# arduino-shield-xyzhbridge-stepper-v1.net
KiCad netlist of a schematic drawn in EAGLE
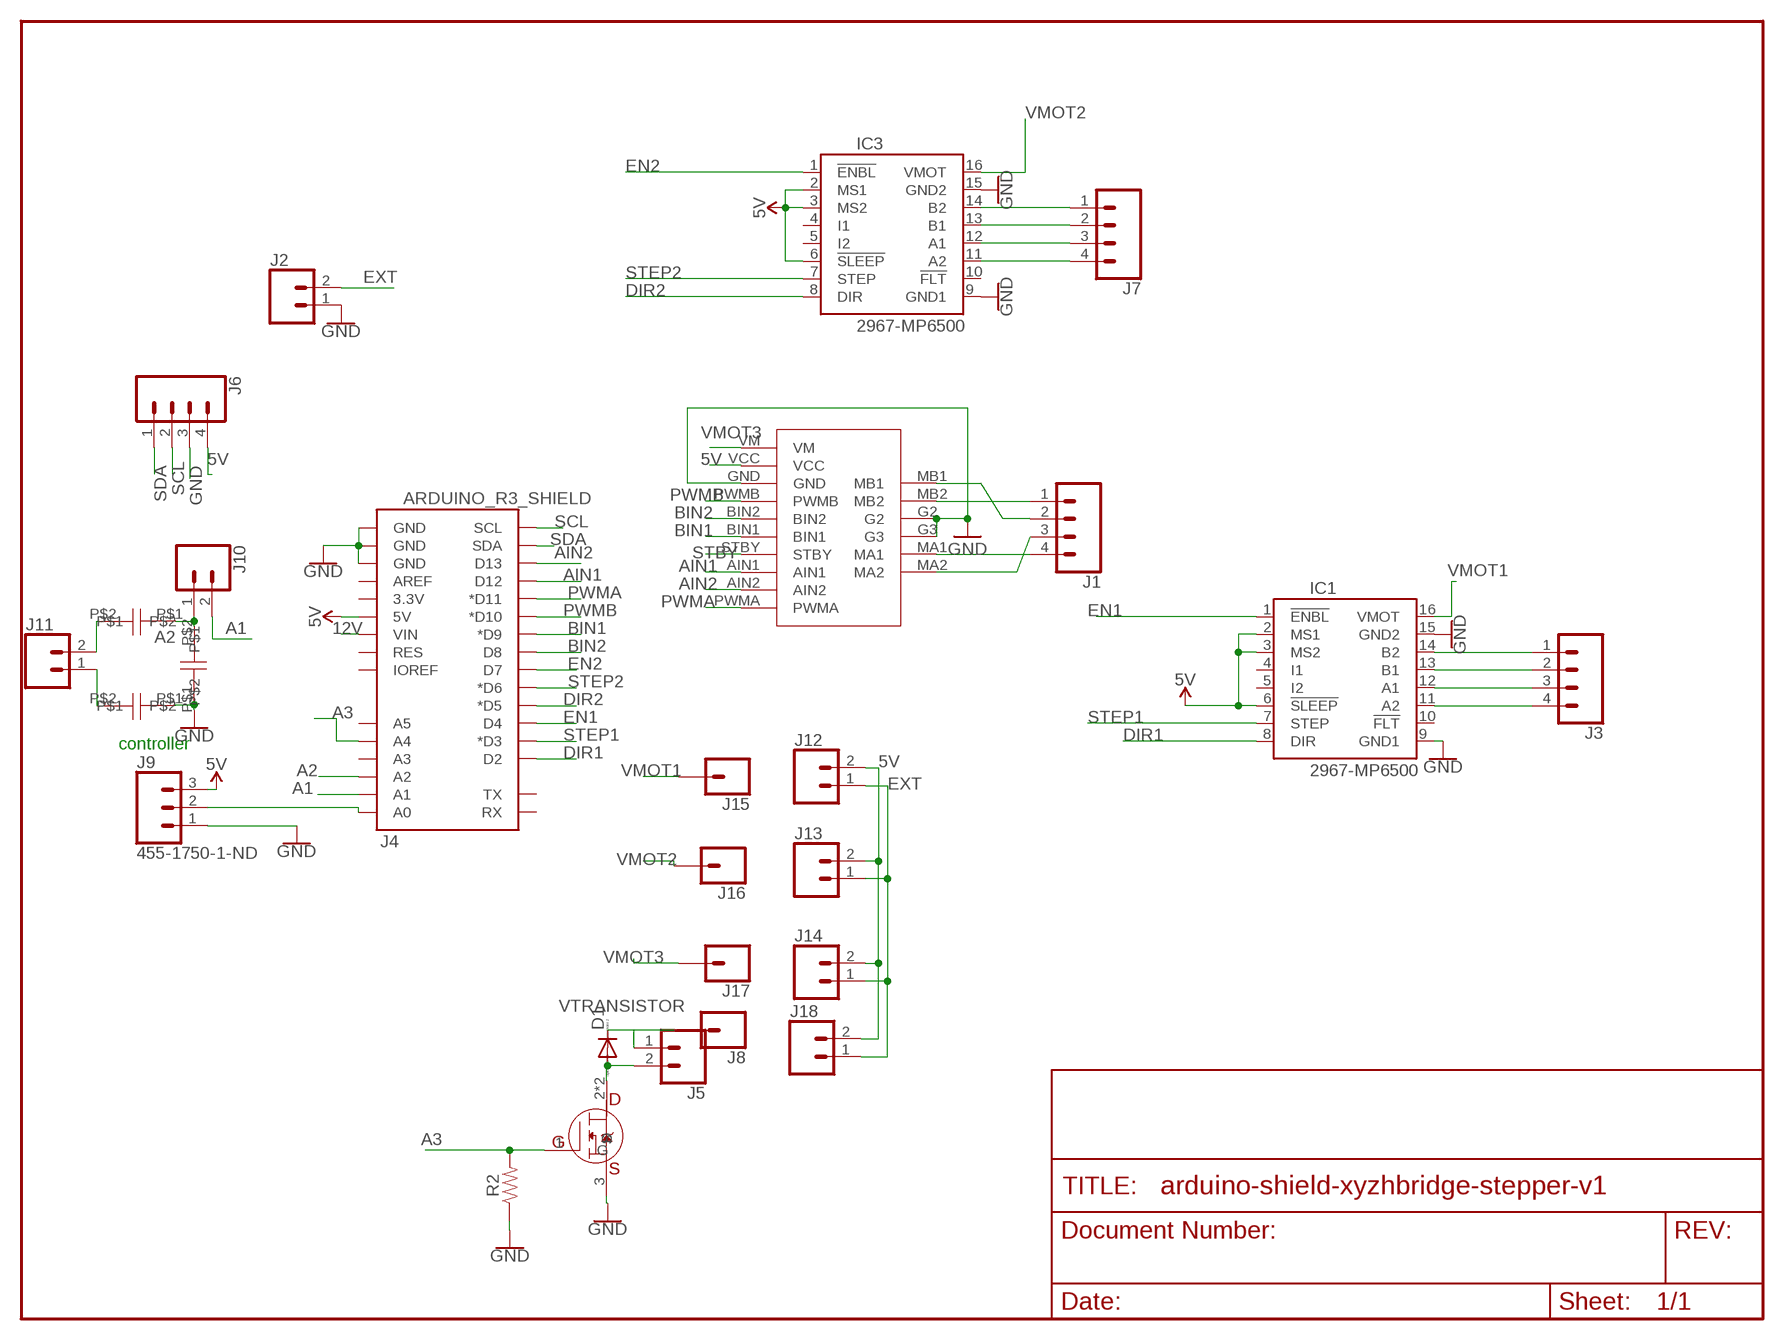
[diagram p0: schematic, sheet 1]

(export (version "E")
  (design (tool "Eeschema 10.0.6"))
  (components
    (comp (ref "D1")
      (value "DIODE-DO-214AC")
      (footprint "eagle-import:DO-214AC")
      (libsource (lib "eagle-import") (part "DIODE-DO-214AC"))
    )
    (comp (ref "IC1")
      (value "2967-MP6500")
      (footprint "eagle-import:MP6500")
      (libsource (lib "eagle-import") (part "2967-MP6500"))
    )
    (comp (ref "IC3")
      (value "2967-MP6500")
      (footprint "eagle-import:MP6500")
      (libsource (lib "eagle-import") (part "2967-MP6500"))
    )
    (comp (ref "J1")
      (value "CONN_04")
      (footprint "eagle-import:1X04")
      (libsource (lib "eagle-import") (part "CONN_04"))
    )
    (comp (ref "J2")
      (value "CONN_02")
      (footprint "eagle-import:1X02")
      (libsource (lib "eagle-import") (part "CONN_02"))
    )
    (comp (ref "J3")
      (value "CONN_04")
      (footprint "eagle-import:1X04")
      (libsource (lib "eagle-import") (part "CONN_04"))
    )
    (comp (ref "J4")
      (value "ARDUINO_R3_SHIELD")
      (footprint "eagle-import:UNO_R3_SHIELD")
      (libsource (lib "eagle-import") (part "ARDUINO_R3_SHIELD"))
    )
    (comp (ref "J5")
      (value "CONN_02")
      (footprint "eagle-import:1X02")
      (libsource (lib "eagle-import") (part "CONN_02"))
    )
    (comp (ref "J6")
      (value "CONN_04")
      (footprint "eagle-import:1X04")
      (libsource (lib "eagle-import") (part "CONN_04"))
    )
    (comp (ref "J7")
      (value "CONN_04")
      (footprint "eagle-import:1X04")
      (libsource (lib "eagle-import") (part "CONN_04"))
    )
    (comp (ref "J8")
      (value "CONN_01")
      (footprint "eagle-import:1X01")
      (libsource (lib "eagle-import") (part "CONN_01"))
    )
    (comp (ref "J9")
      (value "455-1750-1-ND")
      (footprint "eagle-import:1X03")
      (libsource (lib "eagle-import") (part "CONN_03"))
    )
    (comp (ref "J10")
      (value "CONN_02")
      (footprint "eagle-import:1X02")
      (libsource (lib "eagle-import") (part "CONN_02"))
    )
    (comp (ref "J11")
      (value "CONN_02")
      (footprint "eagle-import:1X02")
      (libsource (lib "eagle-import") (part "CONN_02"))
    )
    (comp (ref "J12")
      (value "CONN_02")
      (footprint "eagle-import:1X02")
      (libsource (lib "eagle-import") (part "CONN_02"))
    )
    (comp (ref "J13")
      (value "CONN_02")
      (footprint "eagle-import:1X02")
      (libsource (lib "eagle-import") (part "CONN_02"))
    )
    (comp (ref "J14")
      (value "CONN_02")
      (footprint "eagle-import:1X02")
      (libsource (lib "eagle-import") (part "CONN_02"))
    )
    (comp (ref "J15")
      (value "CONN_01")
      (footprint "eagle-import:1X01")
      (libsource (lib "eagle-import") (part "CONN_01"))
    )
    (comp (ref "J16")
      (value "CONN_01")
      (footprint "eagle-import:1X01")
      (libsource (lib "eagle-import") (part "CONN_01"))
    )
    (comp (ref "J17")
      (value "CONN_01")
      (footprint "eagle-import:1X01")
      (libsource (lib "eagle-import") (part "CONN_01"))
    )
    (comp (ref "J18")
      (value "CONN_02")
      (footprint "eagle-import:1X02")
      (libsource (lib "eagle-import") (part "CONN_02"))
    )
    (comp (ref "R2")
      (value "RESISTORAXIAL-0.3")
      (footprint "eagle-import:AXIAL-0.3")
      (libsource (lib "eagle-import") (part "RESISTORAXIAL-0.3"))
    )
    (comp (ref "U$1")
      (value "ADAFRUIT-TB6612")
      (footprint "eagle-import:ADAFRUIT-TB6612")
      (libsource (lib "eagle-import") (part "ADAFRUIT-TB6612"))
    )
    (comp (ref "U$2")
      (value "AXIALCAP")
      (footprint "eagle-import:AXIALCAP")
      (libsource (lib "eagle-import") (part "AXIALCAP"))
    )
    (comp (ref "U$3")
      (value "AXIALCAP")
      (footprint "eagle-import:AXIALCAP")
      (libsource (lib "eagle-import") (part "AXIALCAP"))
    )
    (comp (ref "U$4")
      (value "AXIALCAP")
      (footprint "eagle-import:AXIALCAP")
      (libsource (lib "eagle-import") (part "AXIALCAP"))
    )
    (comp (ref "U$5")
      (value "IRFL024NPBF")
      (footprint "eagle-import:SOT223")
      (libsource (lib "eagle-import") (part "IRFL024NPBF"))
    )
  )
  (nets
    (net (code "1") (name "/12V") (class "Default")
      (node (ref "J4") (pin "VIN") (pinfunction "VIN_VIN") (pintype "bidirectional"))
    )
    (net (code "2") (name "/A1") (class "Default")
      (node (ref "J10") (pin "2") (pinfunction "2_2") (pintype "passive"))
      (node (ref "J4") (pin "A1") (pinfunction "A1_A1") (pintype "bidirectional"))
    )
    (net (code "3") (name "/A2") (class "Default")
      (node (ref "J10") (pin "1") (pinfunction "1_1") (pintype "passive"))
      (node (ref "J4") (pin "A2") (pinfunction "A2_A2") (pintype "bidirectional"))
      (node (ref "U$3") (pin "P$2") (pinfunction "P$2_P$2") (pintype "bidirectional"))
      (node (ref "U$4") (pin "P$1") (pinfunction "P$1_P$1") (pintype "bidirectional"))
    )
    (net (code "4") (name "/A3") (class "Default")
      (node (ref "J4") (pin "A4") (pinfunction "A4_A4") (pintype "bidirectional"))
      (node (ref "R2") (pin "P$2") (pinfunction "2_P$2") (pintype "passive"))
      (node (ref "U$5") (pin "1") (pinfunction "G_1") (pintype "bidirectional"))
    )
    (net (code "5") (name "/AIN1") (class "Default")
      (node (ref "J4") (pin "D12") (pinfunction "D12_D12") (pintype "bidirectional"))
      (node (ref "U$1") (pin "AIN1") (pinfunction "AIN1_AIN1") (pintype "bidirectional"))
    )
    (net (code "6") (name "/AIN2") (class "Default")
      (node (ref "J4") (pin "D13") (pinfunction "D13_D13") (pintype "bidirectional"))
      (node (ref "U$1") (pin "AIN2") (pinfunction "AIN2_AIN2") (pintype "bidirectional"))
    )
    (net (code "7") (name "/BIN1") (class "Default")
      (node (ref "J4") (pin "D9") (pinfunction "*D9_D9") (pintype "bidirectional"))
      (node (ref "U$1") (pin "BIN1") (pinfunction "BIN1_BIN1") (pintype "bidirectional"))
    )
    (net (code "8") (name "/BIN2") (class "Default")
      (node (ref "J4") (pin "D8") (pinfunction "D8_D8") (pintype "bidirectional"))
      (node (ref "U$1") (pin "BIN2") (pinfunction "BIN2_BIN2") (pintype "bidirectional"))
    )
    (net (code "9") (name "/DIR1") (class "Default")
      (node (ref "IC1") (pin "8") (pinfunction "DIR_8") (pintype "input"))
      (node (ref "J4") (pin "D2") (pinfunction "D2_D2") (pintype "bidirectional"))
    )
    (net (code "10") (name "/DIR2") (class "Default")
      (node (ref "IC3") (pin "8") (pinfunction "DIR_8") (pintype "input"))
      (node (ref "J4") (pin "D5") (pinfunction "*D5_D5") (pintype "bidirectional"))
    )
    (net (code "11") (name "/EN1") (class "Default")
      (node (ref "IC1") (pin "1") (pinfunction "~{ENBL}_1") (pintype "passive"))
      (node (ref "J4") (pin "D4") (pinfunction "D4_D4") (pintype "bidirectional"))
    )
    (net (code "12") (name "/EN2") (class "Default")
      (node (ref "IC3") (pin "1") (pinfunction "~{ENBL}_1") (pintype "passive"))
      (node (ref "J4") (pin "D7") (pinfunction "D7_D7") (pintype "bidirectional"))
    )
    (net (code "13") (name "/EXT") (class "Default")
      (node (ref "J12") (pin "1") (pinfunction "1_1") (pintype "passive"))
      (node (ref "J13") (pin "1") (pinfunction "1_1") (pintype "passive"))
      (node (ref "J14") (pin "1") (pinfunction "1_1") (pintype "passive"))
      (node (ref "J18") (pin "1") (pinfunction "1_1") (pintype "passive"))
      (node (ref "J2") (pin "2") (pinfunction "2_2") (pintype "passive"))
    )
    (net (code "14") (name "/PWMA") (class "Default")
      (node (ref "J4") (pin "D11") (pinfunction "*D11_D11") (pintype "bidirectional"))
      (node (ref "U$1") (pin "PWMA") (pinfunction "PWMA_PWMA") (pintype "bidirectional"))
    )
    (net (code "15") (name "/PWMB") (class "Default")
      (node (ref "J4") (pin "D10") (pinfunction "*D10_D10") (pintype "bidirectional"))
      (node (ref "U$1") (pin "PWMB") (pinfunction "PWMB_PWMB") (pintype "bidirectional"))
    )
    (net (code "16") (name "/SCL") (class "Default")
      (node (ref "J4") (pin "SCL") (pinfunction "SCL_SCL") (pintype "bidirectional"))
      (node (ref "J6") (pin "2") (pinfunction "2_2") (pintype "passive"))
    )
    (net (code "17") (name "/SDA") (class "Default")
      (node (ref "J4") (pin "SDA") (pinfunction "SDA_SDA") (pintype "bidirectional"))
      (node (ref "J6") (pin "1") (pinfunction "1_1") (pintype "passive"))
    )
    (net (code "18") (name "/STBY") (class "Default")
      (node (ref "U$1") (pin "STBY") (pinfunction "STBY_STBY") (pintype "bidirectional"))
    )
    (net (code "19") (name "/STEP1") (class "Default")
      (node (ref "IC1") (pin "7") (pinfunction "STEP_7") (pintype "input"))
      (node (ref "J4") (pin "D3") (pinfunction "*D3_D3") (pintype "bidirectional"))
    )
    (net (code "20") (name "/STEP2") (class "Default")
      (node (ref "IC3") (pin "7") (pinfunction "STEP_7") (pintype "input"))
      (node (ref "J4") (pin "D6") (pinfunction "*D6_D6") (pintype "bidirectional"))
    )
    (net (code "21") (name "/VMOT1") (class "Default")
      (node (ref "IC1") (pin "16") (pinfunction "VMOT_16") (pintype "power_in"))
      (node (ref "J15") (pin "1") (pinfunction "1_1") (pintype "passive"))
    )
    (net (code "22") (name "/VMOT2") (class "Default")
      (node (ref "IC3") (pin "16") (pinfunction "VMOT_16") (pintype "power_in"))
      (node (ref "J16") (pin "1") (pinfunction "1_1") (pintype "passive"))
    )
    (net (code "23") (name "/VMOT3") (class "Default")
      (node (ref "J17") (pin "1") (pinfunction "1_1") (pintype "passive"))
      (node (ref "U$1") (pin "VM") (pinfunction "VM_VM") (pintype "bidirectional"))
    )
    (net (code "24") (name "/VTRANSISTOR") (class "Default")
      (node (ref "D1") (pin "C") (pinfunction "C_C") (pintype "passive"))
      (node (ref "J5") (pin "1") (pinfunction "1_1") (pintype "passive"))
      (node (ref "J8") (pin "1") (pinfunction "1_1") (pintype "passive"))
    )
    (net (code "25") (name "5V") (class "Default")
      (node (ref "IC1") (pin "2") (pinfunction "MS1_2") (pintype "passive"))
      (node (ref "IC1") (pin "3") (pinfunction "MS2_3") (pintype "passive"))
      (node (ref "IC1") (pin "6") (pinfunction "~{SLEEP}_6") (pintype "input"))
      (node (ref "IC3") (pin "2") (pinfunction "MS1_2") (pintype "passive"))
      (node (ref "IC3") (pin "3") (pinfunction "MS2_3") (pintype "passive"))
      (node (ref "IC3") (pin "6") (pinfunction "~{SLEEP}_6") (pintype "input"))
      (node (ref "J12") (pin "2") (pinfunction "2_2") (pintype "passive"))
      (node (ref "J13") (pin "2") (pinfunction "2_2") (pintype "passive"))
      (node (ref "J14") (pin "2") (pinfunction "2_2") (pintype "passive"))
      (node (ref "J18") (pin "2") (pinfunction "2_2") (pintype "passive"))
      (node (ref "J4") (pin "5V") (pinfunction "5V_5V") (pintype "bidirectional"))
      (node (ref "J6") (pin "4") (pinfunction "4_4") (pintype "passive"))
      (node (ref "J9") (pin "3") (pinfunction "3_3") (pintype "passive"))
      (node (ref "U$1") (pin "VCC") (pinfunction "VCC_VCC") (pintype "bidirectional"))
    )
    (net (code "26") (name "GND") (class "Default")
      (node (ref "IC1") (pin "15") (pinfunction "GND2_15") (pintype "power_in"))
      (node (ref "IC1") (pin "9") (pinfunction "GND1_9") (pintype "power_in"))
      (node (ref "IC3") (pin "15") (pinfunction "GND2_15") (pintype "power_in"))
      (node (ref "IC3") (pin "9") (pinfunction "GND1_9") (pintype "power_in"))
      (node (ref "J2") (pin "1") (pinfunction "1_1") (pintype "passive"))
      (node (ref "J4") (pin "GND@0") (pinfunction "GND_GND@0") (pintype "bidirectional"))
      (node (ref "J4") (pin "GND@1") (pinfunction "GND_GND@1") (pintype "bidirectional"))
      (node (ref "J4") (pin "GND@2") (pinfunction "GND_GND@2") (pintype "bidirectional"))
      (node (ref "J6") (pin "3") (pinfunction "3_3") (pintype "passive"))
      (node (ref "J9") (pin "1") (pinfunction "1_1") (pintype "passive"))
      (node (ref "R2") (pin "P$1") (pinfunction "1_P$1") (pintype "passive"))
      (node (ref "U$1") (pin "G2") (pinfunction "G2_G2") (pintype "bidirectional"))
      (node (ref "U$1") (pin "G3") (pinfunction "G3_G3") (pintype "bidirectional"))
      (node (ref "U$1") (pin "GND") (pinfunction "GND_GND") (pintype "bidirectional"))
      (node (ref "U$2") (pin "P$1") (pinfunction "P$1_P$1") (pintype "bidirectional"))
      (node (ref "U$3") (pin "P$1") (pinfunction "P$1_P$1") (pintype "bidirectional"))
      (node (ref "U$5") (pin "3") (pinfunction "S_3") (pintype "bidirectional"))
    )
    (net (code "27") (name "Net-(D1-PadA)") (class "Default")
      (node (ref "D1") (pin "A") (pinfunction "A_A") (pintype "passive"))
      (node (ref "J5") (pin "2") (pinfunction "2_2") (pintype "passive"))
      (node (ref "U$5") (pin "2") (pinfunction "D_2") (pintype "bidirectional"))
      (node (ref "U$5") (pin "4") (pinfunction "D_4") (pintype "bidirectional"))
    )
    (net (code "28") (name "Net-(IC1-A1)") (class "Default")
      (node (ref "IC1") (pin "12") (pinfunction "A1_12") (pintype "output"))
      (node (ref "J3") (pin "3") (pinfunction "3_3") (pintype "passive"))
    )
    (net (code "29") (name "Net-(IC1-A2)") (class "Default")
      (node (ref "IC1") (pin "11") (pinfunction "A2_11") (pintype "output"))
      (node (ref "J3") (pin "4") (pinfunction "4_4") (pintype "passive"))
    )
    (net (code "30") (name "Net-(IC1-B1)") (class "Default")
      (node (ref "IC1") (pin "13") (pinfunction "B1_13") (pintype "output"))
      (node (ref "J3") (pin "2") (pinfunction "2_2") (pintype "passive"))
    )
    (net (code "31") (name "Net-(IC1-B2)") (class "Default")
      (node (ref "IC1") (pin "14") (pinfunction "B2_14") (pintype "output"))
      (node (ref "J3") (pin "1") (pinfunction "1_1") (pintype "passive"))
    )
    (net (code "32") (name "Net-(IC3-A1)") (class "Default")
      (node (ref "IC3") (pin "12") (pinfunction "A1_12") (pintype "output"))
      (node (ref "J7") (pin "3") (pinfunction "3_3") (pintype "passive"))
    )
    (net (code "33") (name "Net-(IC3-A2)") (class "Default")
      (node (ref "IC3") (pin "11") (pinfunction "A2_11") (pintype "output"))
      (node (ref "J7") (pin "4") (pinfunction "4_4") (pintype "passive"))
    )
    (net (code "34") (name "Net-(IC3-B1)") (class "Default")
      (node (ref "IC3") (pin "13") (pinfunction "B1_13") (pintype "output"))
      (node (ref "J7") (pin "2") (pinfunction "2_2") (pintype "passive"))
    )
    (net (code "35") (name "Net-(IC3-B2)") (class "Default")
      (node (ref "IC3") (pin "14") (pinfunction "B2_14") (pintype "output"))
      (node (ref "J7") (pin "1") (pinfunction "1_1") (pintype "passive"))
    )
    (net (code "36") (name "Net-(J1-Pad1)") (class "Default")
      (node (ref "J1") (pin "1") (pinfunction "1_1") (pintype "passive"))
      (node (ref "U$1") (pin "MB2") (pinfunction "MB2_MB2") (pintype "bidirectional"))
    )
    (net (code "37") (name "Net-(J1-Pad2)") (class "Default")
      (node (ref "J1") (pin "2") (pinfunction "2_2") (pintype "passive"))
      (node (ref "U$1") (pin "MB1") (pinfunction "MB1_MB1") (pintype "bidirectional"))
    )
    (net (code "38") (name "Net-(J1-Pad3)") (class "Default")
      (node (ref "J1") (pin "3") (pinfunction "3_3") (pintype "passive"))
      (node (ref "U$1") (pin "MA2") (pinfunction "MA2_MA2") (pintype "bidirectional"))
    )
    (net (code "39") (name "Net-(J1-Pad4)") (class "Default")
      (node (ref "J1") (pin "4") (pinfunction "4_4") (pintype "passive"))
      (node (ref "U$1") (pin "MA1") (pinfunction "MA1_MA1") (pintype "bidirectional"))
    )
    (net (code "40") (name "Net-(J4-PadA0)") (class "Default")
      (node (ref "J4") (pin "A0") (pinfunction "A0_A0") (pintype "bidirectional"))
      (node (ref "J9") (pin "2") (pinfunction "2_2") (pintype "passive"))
    )
    (net (code "41") (name "Net-(J11-Pad1)") (class "Default")
      (node (ref "J11") (pin "1") (pinfunction "1_1") (pintype "passive"))
      (node (ref "U$2") (pin "P$2") (pinfunction "P$2_P$2") (pintype "bidirectional"))
    )
    (net (code "42") (name "Net-(J11-Pad2)") (class "Default")
      (node (ref "J11") (pin "2") (pinfunction "2_2") (pintype "passive"))
      (node (ref "U$4") (pin "P$2") (pinfunction "P$2_P$2") (pintype "bidirectional"))
    )
    (net (code "43") (name "unconnected-(IC1-I1-Pad4)") (class "Default")
      (node (ref "IC1") (pin "4") (pinfunction "I1_4") (pintype "passive"))
    )
    (net (code "44") (name "unconnected-(IC1-I2-Pad5)") (class "Default")
      (node (ref "IC1") (pin "5") (pinfunction "I2_5") (pintype "passive"))
    )
    (net (code "45") (name "unconnected-(IC1-~{FLT}-Pad10)") (class "Default")
      (node (ref "IC1") (pin "10") (pinfunction "~{FLT}_10") (pintype "open_collector"))
    )
    (net (code "46") (name "unconnected-(IC3-I1-Pad4)") (class "Default")
      (node (ref "IC3") (pin "4") (pinfunction "I1_4") (pintype "passive"))
    )
    (net (code "47") (name "unconnected-(IC3-I2-Pad5)") (class "Default")
      (node (ref "IC3") (pin "5") (pinfunction "I2_5") (pintype "passive"))
    )
    (net (code "48") (name "unconnected-(IC3-~{FLT}-Pad10)") (class "Default")
      (node (ref "IC3") (pin "10") (pinfunction "~{FLT}_10") (pintype "open_collector"))
    )
    (net (code "49") (name "unconnected-(J4-Pad3.3V)") (class "Default")
      (node (ref "J4") (pin "3.3V") (pinfunction "3.3V_3.3V") (pintype "bidirectional"))
    )
    (net (code "50") (name "unconnected-(J4-PadA3)") (class "Default")
      (node (ref "J4") (pin "A3") (pinfunction "A3_A3") (pintype "bidirectional"))
    )
    (net (code "51") (name "unconnected-(J4-PadA5)") (class "Default")
      (node (ref "J4") (pin "A5") (pinfunction "A5_A5") (pintype "bidirectional"))
    )
    (net (code "52") (name "unconnected-(J4-PadAREF)") (class "Default")
      (node (ref "J4") (pin "AREF") (pinfunction "AREF_AREF") (pintype "bidirectional"))
    )
    (net (code "53") (name "unconnected-(J4-PadIOREF)") (class "Default")
      (node (ref "J4") (pin "IOREF") (pinfunction "IOREF_IOREF") (pintype "bidirectional"))
    )
    (net (code "54") (name "unconnected-(J4-PadRES)") (class "Default")
      (node (ref "J4") (pin "RES") (pinfunction "RES_RES") (pintype "bidirectional"))
    )
    (net (code "55") (name "unconnected-(J4-PadRX)") (class "Default")
      (node (ref "J4") (pin "RX") (pinfunction "RX_RX") (pintype "bidirectional"))
    )
    (net (code "56") (name "unconnected-(J4-PadTX)") (class "Default")
      (node (ref "J4") (pin "TX") (pinfunction "TX_TX") (pintype "bidirectional"))
    )
  )
)
